# SCH_ENAK-display_2025-10-05.net
KiCad netlist of a schematic drawn in EasyEDA
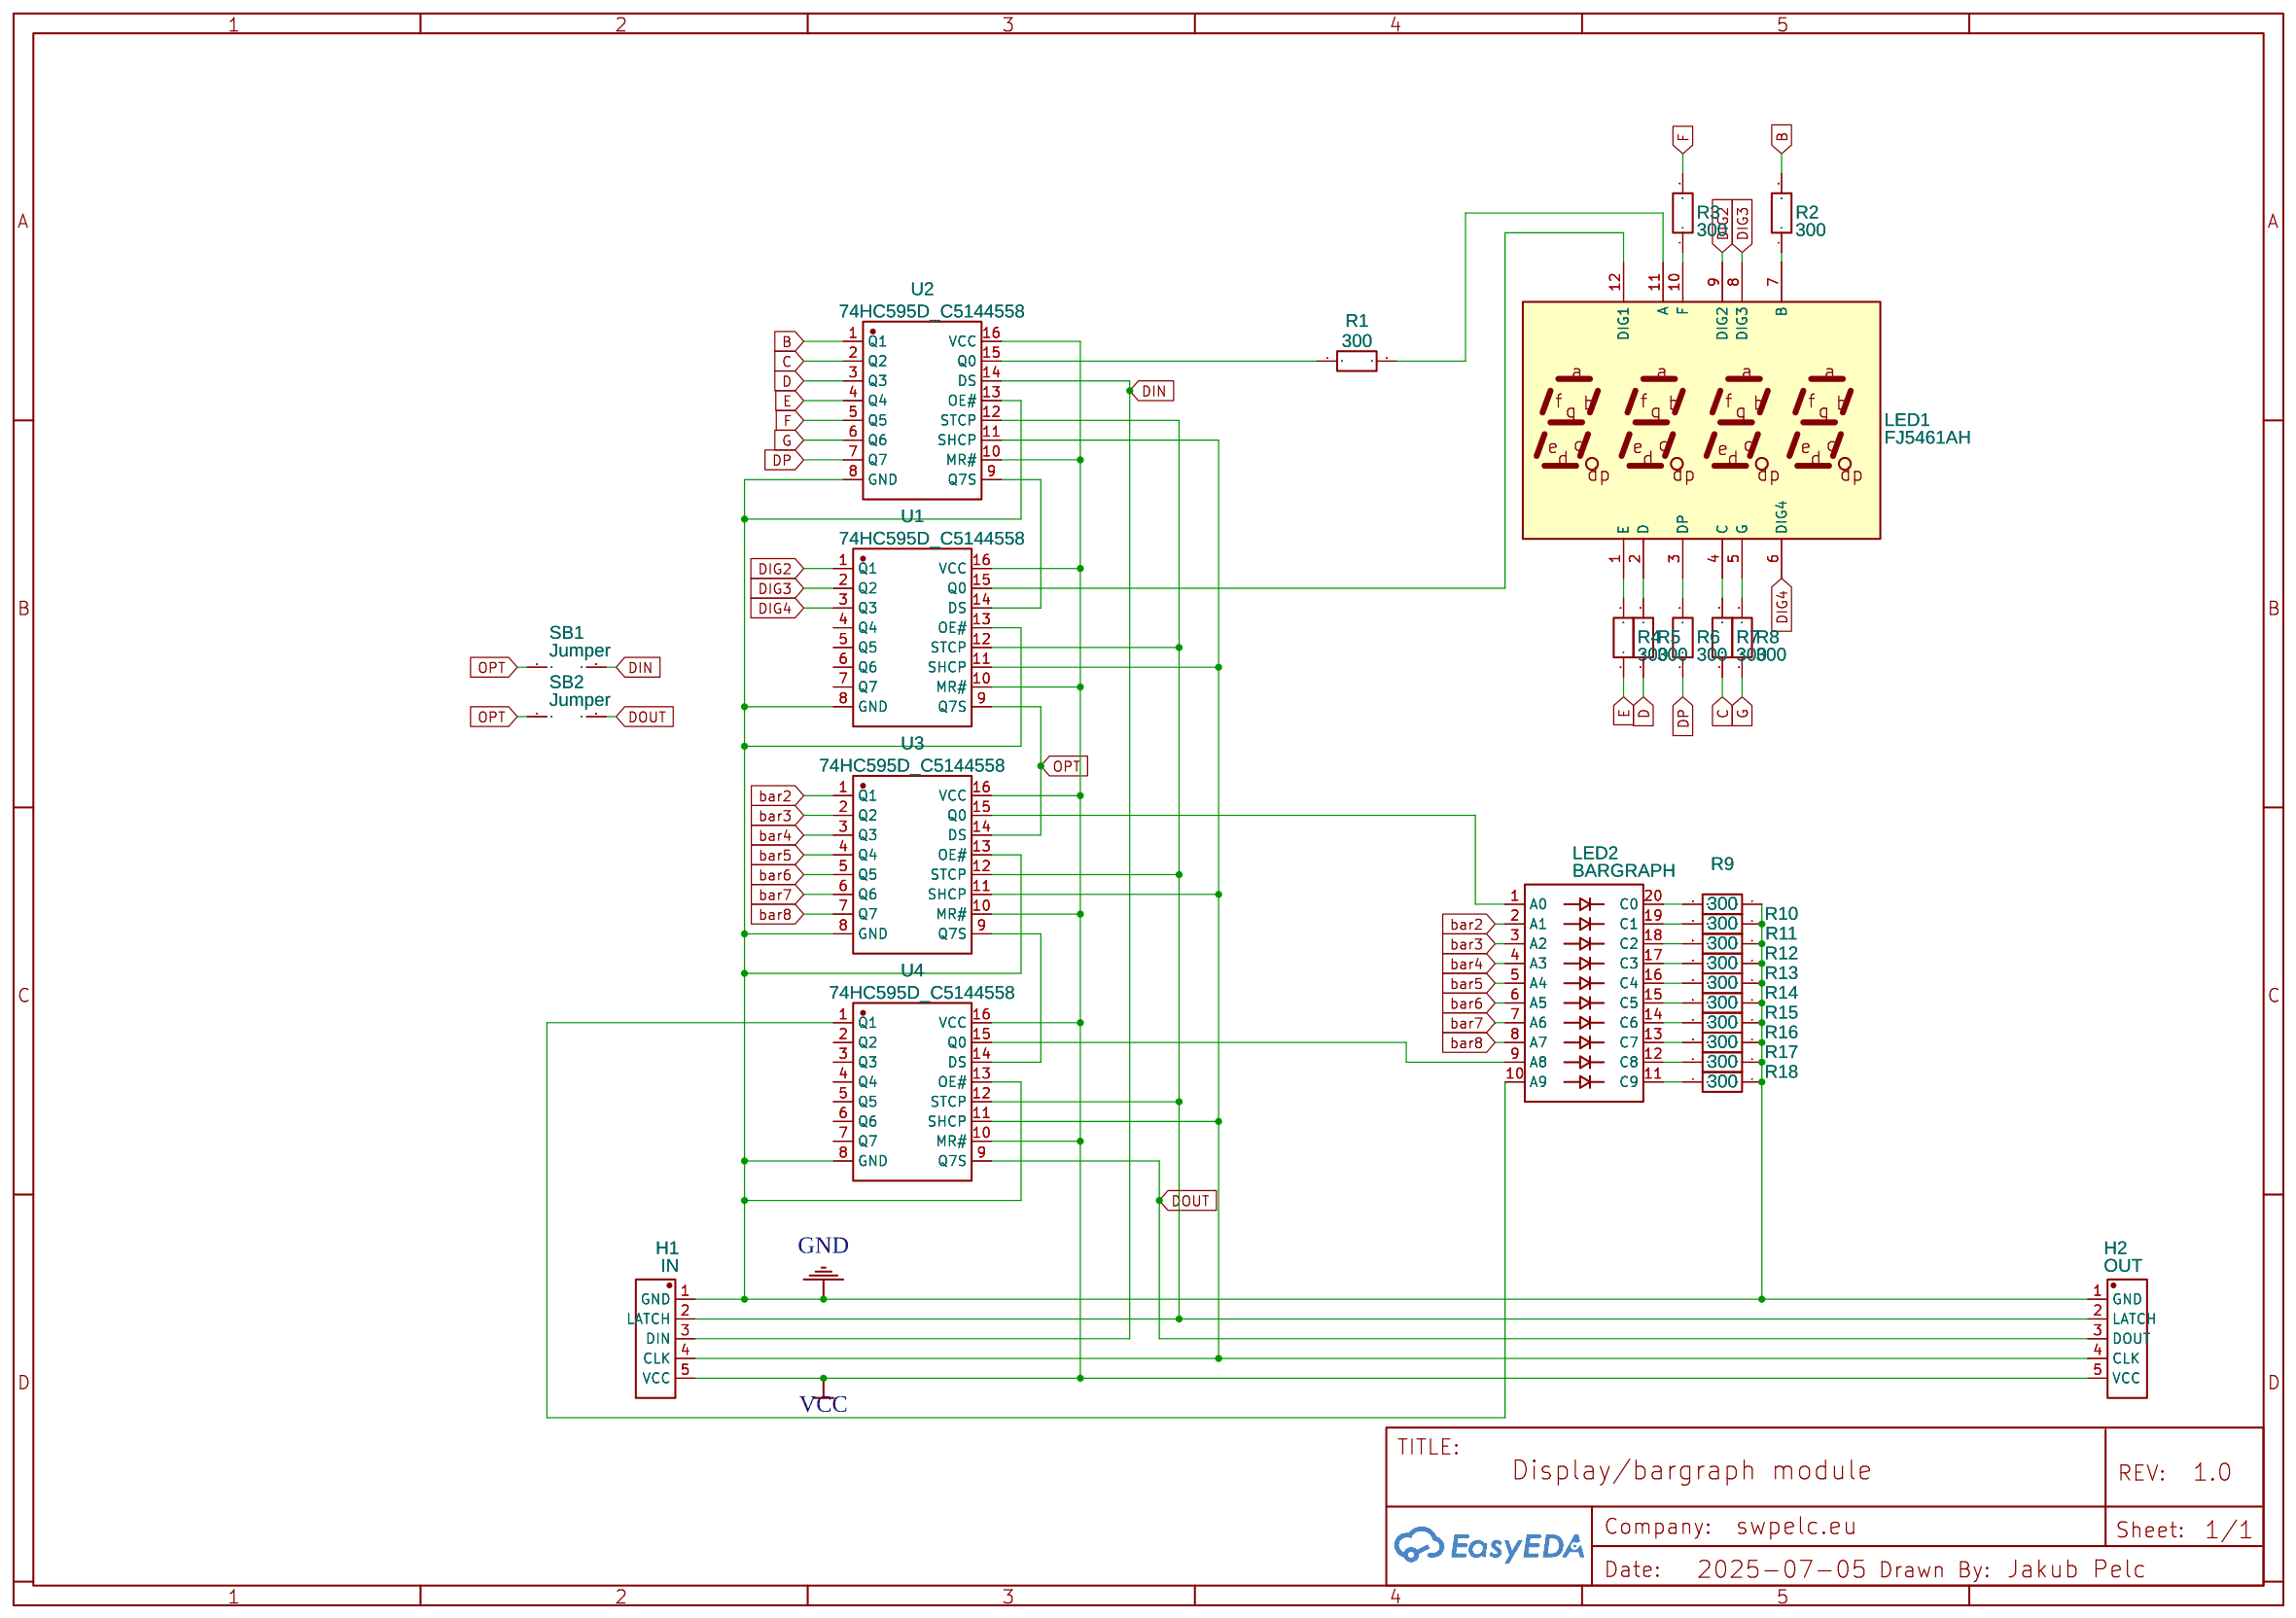
[diagram p0: schematic sheet]

(export (version "E")
  (design (tool "Eeschema 10.0.6"))
  (components
    (comp (ref "H1") (value "IN") (libsource (lib "") (part "HEADER - 2.54_1X5_1")))
    (comp (ref "H2") (value "OUT") (libsource (lib "") (part "HEADER - 2.54_1X5")))
    (comp (ref "LED1")
      (value "FJ5461AH")
      (fields (field (name "Manufacturer Part") "FJ5461AH 橙红") (field (name "Manufacturer") "志浩"))
      (libsource (lib "") (part "FJ5461AH"))
    )
    (comp (ref "LED2") (value "BARGRAPH") (libsource (lib "") (part "BARGRAPH")))
    (comp (ref "R1") (value "300") (libsource (lib "") (part "R_0603_EU_2")))
    (comp (ref "R2") (value "300") (libsource (lib "") (part "R_0603_EU_1")))
    (comp (ref "R3") (value "300") (libsource (lib "") (part "R_0603_EU_1")))
    (comp (ref "R4") (value "300") (libsource (lib "") (part "R_0603_EU_1")))
    (comp (ref "R5") (value "300") (libsource (lib "") (part "R_0603_EU_1")))
    (comp (ref "R6") (value "300") (libsource (lib "") (part "R_0603_EU_1")))
    (comp (ref "R7") (value "300") (libsource (lib "") (part "R_0603_EU_1")))
    (comp (ref "R8") (value "300") (libsource (lib "") (part "R_0603_EU_1")))
    (comp (ref "R9") (value "300") (libsource (lib "") (part "R_0603_EU")))
    (comp (ref "R10") (value "300") (libsource (lib "") (part "R_0603_EU")))
    (comp (ref "R11") (value "300") (libsource (lib "") (part "R_0603_EU")))
    (comp (ref "R12") (value "300") (libsource (lib "") (part "R_0603_EU")))
    (comp (ref "R13") (value "300") (libsource (lib "") (part "R_0603_EU")))
    (comp (ref "R14") (value "300") (libsource (lib "") (part "R_0603_EU")))
    (comp (ref "R15") (value "300") (libsource (lib "") (part "R_0603_EU")))
    (comp (ref "R16") (value "300") (libsource (lib "") (part "R_0603_EU")))
    (comp (ref "R17") (value "300") (libsource (lib "") (part "R_0603_EU")))
    (comp (ref "R18") (value "300") (libsource (lib "") (part "R_0603_EU")))
    (comp (ref "SB1")
      (value "Jumper")
      (fields (field (name "Manufacturer Part") "0603WAF0000T5E") (field (name "Manufacturer") "NONE"))
      (libsource (lib "") (part "SMD JUMPER OPEN 2 PIN"))
    )
    (comp (ref "SB2")
      (value "Jumper")
      (fields (field (name "Manufacturer Part") "0603WAF0000T5E") (field (name "Manufacturer") "NONE"))
      (libsource (lib "") (part "SMD JUMPER OPEN 2 PIN"))
    )
    (comp (ref "U1")
      (value "74HC595D_C5144558")
      (fields (field (name "Manufacturer Part") "74HC595D") (field (name "Manufacturer") "JSMSEMI(杰盛微)"))
      (libsource (lib "") (part "74HC595D_C5144558"))
    )
    (comp (ref "U2")
      (value "74HC595D_C5144558")
      (fields (field (name "Manufacturer Part") "74HC595D") (field (name "Manufacturer") "JSMSEMI(杰盛微)"))
      (libsource (lib "") (part "74HC595D_C5144558"))
    )
    (comp (ref "U3")
      (value "74HC595D_C5144558")
      (fields (field (name "Manufacturer Part") "74HC595D") (field (name "Manufacturer") "JSMSEMI(杰盛微)"))
      (libsource (lib "") (part "74HC595D_C5144558"))
    )
    (comp (ref "U4")
      (value "74HC595D_C5144558")
      (fields (field (name "Manufacturer Part") "74HC595D") (field (name "Manufacturer") "JSMSEMI(杰盛微)"))
      (libsource (lib "") (part "74HC595D_C5144558"))
    )
  )
  (nets
    (net (code "1") (name "B") (class "Default")
      (node (ref "R2") (pin "2") (pinfunction "2_2") (pintype "unspecified"))
      (node (ref "U2") (pin "1") (pinfunction "Q1_1") (pintype "unspecified"))
    )
    (net (code "2") (name "C") (class "Default")
      (node (ref "R7") (pin "1") (pinfunction "1_1") (pintype "unspecified"))
      (node (ref "U2") (pin "2") (pinfunction "Q2_2") (pintype "unspecified"))
    )
    (net (code "3") (name "D") (class "Default")
      (node (ref "R5") (pin "1") (pinfunction "1_1") (pintype "unspecified"))
      (node (ref "U2") (pin "3") (pinfunction "Q3_3") (pintype "unspecified"))
    )
    (net (code "4") (name "DIG2") (class "Default")
      (node (ref "LED1") (pin "9") (pinfunction "DIG2_9") (pintype "input"))
      (node (ref "U1") (pin "1") (pinfunction "Q1_1") (pintype "unspecified"))
    )
    (net (code "5") (name "DIG3") (class "Default")
      (node (ref "LED1") (pin "8") (pinfunction "DIG3_8") (pintype "input"))
      (node (ref "U1") (pin "2") (pinfunction "Q2_2") (pintype "unspecified"))
    )
    (net (code "6") (name "DIG4") (class "Default")
      (node (ref "LED1") (pin "6") (pinfunction "DIG4_6") (pintype "input"))
      (node (ref "U1") (pin "3") (pinfunction "Q3_3") (pintype "unspecified"))
    )
    (net (code "7") (name "DIN") (class "Default")
      (node (ref "H1") (pin "3") (pinfunction "DIN_3") (pintype "unspecified"))
      (node (ref "SB1") (pin "2") (pinfunction "N_2") (pintype "input"))
      (node (ref "U2") (pin "14") (pinfunction "DS_14") (pintype "unspecified"))
    )
    (net (code "8") (name "DOUT") (class "Default")
      (node (ref "H2") (pin "3") (pinfunction "DOUT_3") (pintype "unspecified"))
      (node (ref "SB2") (pin "2") (pinfunction "N_2") (pintype "input"))
      (node (ref "U4") (pin "9") (pinfunction "Q7S_9") (pintype "unspecified"))
    )
    (net (code "9") (name "DP") (class "Default")
      (node (ref "R6") (pin "1") (pinfunction "1_1") (pintype "unspecified"))
      (node (ref "U2") (pin "7") (pinfunction "Q7_7") (pintype "unspecified"))
    )
    (net (code "10") (name "E") (class "Default")
      (node (ref "R4") (pin "1") (pinfunction "1_1") (pintype "unspecified"))
      (node (ref "U2") (pin "4") (pinfunction "Q4_4") (pintype "unspecified"))
    )
    (net (code "11") (name "F") (class "Default")
      (node (ref "R3") (pin "2") (pinfunction "2_2") (pintype "unspecified"))
      (node (ref "U2") (pin "5") (pinfunction "Q5_5") (pintype "unspecified"))
    )
    (net (code "12") (name "G") (class "Default")
      (node (ref "R8") (pin "1") (pinfunction "1_1") (pintype "unspecified"))
      (node (ref "U2") (pin "6") (pinfunction "Q6_6") (pintype "unspecified"))
    )
    (net (code "13") (name "GND") (class "Default")
      (node (ref "H1") (pin "1") (pinfunction "GND_1") (pintype "unspecified"))
      (node (ref "H2") (pin "1") (pinfunction "GND_1") (pintype "unspecified"))
      (node (ref "R10") (pin "1") (pinfunction "1_1") (pintype "unspecified"))
      (node (ref "R11") (pin "1") (pinfunction "1_1") (pintype "unspecified"))
      (node (ref "R12") (pin "1") (pinfunction "1_1") (pintype "unspecified"))
      (node (ref "R13") (pin "1") (pinfunction "1_1") (pintype "unspecified"))
      (node (ref "R14") (pin "1") (pinfunction "1_1") (pintype "unspecified"))
      (node (ref "R15") (pin "1") (pinfunction "1_1") (pintype "unspecified"))
      (node (ref "R16") (pin "1") (pinfunction "1_1") (pintype "unspecified"))
      (node (ref "R17") (pin "1") (pinfunction "1_1") (pintype "unspecified"))
      (node (ref "R18") (pin "1") (pinfunction "1_1") (pintype "unspecified"))
      (node (ref "R9") (pin "1") (pinfunction "1_1") (pintype "unspecified"))
      (node (ref "U1") (pin "13") (pinfunction "OE#_13") (pintype "unspecified"))
      (node (ref "U1") (pin "8") (pinfunction "GND_8") (pintype "unspecified"))
      (node (ref "U2") (pin "13") (pinfunction "OE#_13") (pintype "unspecified"))
      (node (ref "U2") (pin "8") (pinfunction "GND_8") (pintype "unspecified"))
      (node (ref "U3") (pin "13") (pinfunction "OE#_13") (pintype "unspecified"))
      (node (ref "U3") (pin "8") (pinfunction "GND_8") (pintype "unspecified"))
      (node (ref "U4") (pin "13") (pinfunction "OE#_13") (pintype "unspecified"))
      (node (ref "U4") (pin "8") (pinfunction "GND_8") (pintype "unspecified"))
    )
    (net (code "14") (name "Net-(H1-CLK)") (class "Default")
      (node (ref "H1") (pin "4") (pinfunction "CLK_4") (pintype "unspecified"))
      (node (ref "H2") (pin "4") (pinfunction "CLK_4") (pintype "unspecified"))
      (node (ref "U1") (pin "11") (pinfunction "SHCP_11") (pintype "unspecified"))
      (node (ref "U2") (pin "11") (pinfunction "SHCP_11") (pintype "unspecified"))
      (node (ref "U3") (pin "11") (pinfunction "SHCP_11") (pintype "unspecified"))
      (node (ref "U4") (pin "11") (pinfunction "SHCP_11") (pintype "unspecified"))
    )
    (net (code "15") (name "Net-(H1-LATCH)") (class "Default")
      (node (ref "H1") (pin "2") (pinfunction "LATCH_2") (pintype "unspecified"))
      (node (ref "H2") (pin "2") (pinfunction "LATCH_2") (pintype "unspecified"))
      (node (ref "U1") (pin "12") (pinfunction "STCP_12") (pintype "unspecified"))
      (node (ref "U2") (pin "12") (pinfunction "STCP_12") (pintype "unspecified"))
      (node (ref "U3") (pin "12") (pinfunction "STCP_12") (pintype "unspecified"))
      (node (ref "U4") (pin "12") (pinfunction "STCP_12") (pintype "unspecified"))
    )
    (net (code "16") (name "Net-(LED1-A)") (class "Default")
      (node (ref "LED1") (pin "11") (pinfunction "A_11") (pintype "input"))
      (node (ref "R1") (pin "2") (pinfunction "2_2") (pintype "unspecified"))
    )
    (net (code "17") (name "Net-(LED1-B)") (class "Default")
      (node (ref "LED1") (pin "7") (pinfunction "B_7") (pintype "input"))
      (node (ref "R2") (pin "1") (pinfunction "1_1") (pintype "unspecified"))
    )
    (net (code "18") (name "Net-(LED1-C)") (class "Default")
      (node (ref "LED1") (pin "4") (pinfunction "C_4") (pintype "input"))
      (node (ref "R7") (pin "2") (pinfunction "2_2") (pintype "unspecified"))
    )
    (net (code "19") (name "Net-(LED1-D)") (class "Default")
      (node (ref "LED1") (pin "2") (pinfunction "D_2") (pintype "input"))
      (node (ref "R5") (pin "2") (pinfunction "2_2") (pintype "unspecified"))
    )
    (net (code "20") (name "Net-(LED1-DIG1)") (class "Default")
      (node (ref "LED1") (pin "12") (pinfunction "DIG1_12") (pintype "input"))
      (node (ref "U1") (pin "15") (pinfunction "Q0_15") (pintype "unspecified"))
    )
    (net (code "21") (name "Net-(LED1-DP)") (class "Default")
      (node (ref "LED1") (pin "3") (pinfunction "DP_3") (pintype "input"))
      (node (ref "R6") (pin "2") (pinfunction "2_2") (pintype "unspecified"))
    )
    (net (code "22") (name "Net-(LED1-E)") (class "Default")
      (node (ref "LED1") (pin "1") (pinfunction "E_1") (pintype "input"))
      (node (ref "R4") (pin "2") (pinfunction "2_2") (pintype "unspecified"))
    )
    (net (code "23") (name "Net-(LED1-F)") (class "Default")
      (node (ref "LED1") (pin "10") (pinfunction "F_10") (pintype "input"))
      (node (ref "R3") (pin "1") (pinfunction "1_1") (pintype "unspecified"))
    )
    (net (code "24") (name "Net-(LED1-G)") (class "Default")
      (node (ref "LED1") (pin "5") (pinfunction "G_5") (pintype "input"))
      (node (ref "R8") (pin "2") (pinfunction "2_2") (pintype "unspecified"))
    )
    (net (code "25") (name "Net-(LED2-A0)") (class "Default")
      (node (ref "LED2") (pin "1") (pinfunction "A0_1") (pintype "unspecified"))
      (node (ref "U3") (pin "15") (pinfunction "Q0_15") (pintype "unspecified"))
    )
    (net (code "26") (name "Net-(LED2-A8)") (class "Default")
      (node (ref "LED2") (pin "9") (pinfunction "A8_9") (pintype "unspecified"))
      (node (ref "U4") (pin "15") (pinfunction "Q0_15") (pintype "unspecified"))
    )
    (net (code "27") (name "Net-(LED2-A9)") (class "Default")
      (node (ref "LED2") (pin "10") (pinfunction "A9_10") (pintype "unspecified"))
      (node (ref "U4") (pin "1") (pinfunction "Q1_1") (pintype "unspecified"))
    )
    (net (code "28") (name "Net-(LED2-C0)") (class "Default")
      (node (ref "LED2") (pin "20") (pinfunction "C0_20") (pintype "unspecified"))
      (node (ref "R9") (pin "2") (pinfunction "2_2") (pintype "unspecified"))
    )
    (net (code "29") (name "Net-(LED2-C1)") (class "Default")
      (node (ref "LED2") (pin "19") (pinfunction "C1_19") (pintype "unspecified"))
      (node (ref "R10") (pin "2") (pinfunction "2_2") (pintype "unspecified"))
    )
    (net (code "30") (name "Net-(LED2-C2)") (class "Default")
      (node (ref "LED2") (pin "18") (pinfunction "C2_18") (pintype "unspecified"))
      (node (ref "R11") (pin "2") (pinfunction "2_2") (pintype "unspecified"))
    )
    (net (code "31") (name "Net-(LED2-C3)") (class "Default")
      (node (ref "LED2") (pin "17") (pinfunction "C3_17") (pintype "unspecified"))
      (node (ref "R12") (pin "2") (pinfunction "2_2") (pintype "unspecified"))
    )
    (net (code "32") (name "Net-(LED2-C4)") (class "Default")
      (node (ref "LED2") (pin "16") (pinfunction "C4_16") (pintype "unspecified"))
      (node (ref "R13") (pin "2") (pinfunction "2_2") (pintype "unspecified"))
    )
    (net (code "33") (name "Net-(LED2-C5)") (class "Default")
      (node (ref "LED2") (pin "15") (pinfunction "C5_15") (pintype "unspecified"))
      (node (ref "R14") (pin "2") (pinfunction "2_2") (pintype "unspecified"))
    )
    (net (code "34") (name "Net-(LED2-C6)") (class "Default")
      (node (ref "LED2") (pin "14") (pinfunction "C6_14") (pintype "unspecified"))
      (node (ref "R15") (pin "2") (pinfunction "2_2") (pintype "unspecified"))
    )
    (net (code "35") (name "Net-(LED2-C7)") (class "Default")
      (node (ref "LED2") (pin "13") (pinfunction "C7_13") (pintype "unspecified"))
      (node (ref "R16") (pin "2") (pinfunction "2_2") (pintype "unspecified"))
    )
    (net (code "36") (name "Net-(LED2-C8)") (class "Default")
      (node (ref "LED2") (pin "12") (pinfunction "C8_12") (pintype "unspecified"))
      (node (ref "R17") (pin "2") (pinfunction "2_2") (pintype "unspecified"))
    )
    (net (code "37") (name "Net-(LED2-C9)") (class "Default")
      (node (ref "LED2") (pin "11") (pinfunction "C9_11") (pintype "unspecified"))
      (node (ref "R18") (pin "2") (pinfunction "2_2") (pintype "unspecified"))
    )
    (net (code "38") (name "Net-(U1-DS)") (class "Default")
      (node (ref "U1") (pin "14") (pinfunction "DS_14") (pintype "unspecified"))
      (node (ref "U2") (pin "9") (pinfunction "Q7S_9") (pintype "unspecified"))
    )
    (net (code "39") (name "Net-(U2-Q0)") (class "Default")
      (node (ref "R1") (pin "1") (pinfunction "1_1") (pintype "unspecified"))
      (node (ref "U2") (pin "15") (pinfunction "Q0_15") (pintype "unspecified"))
    )
    (net (code "40") (name "Net-(U3-Q7S)") (class "Default")
      (node (ref "U3") (pin "9") (pinfunction "Q7S_9") (pintype "unspecified"))
      (node (ref "U4") (pin "14") (pinfunction "DS_14") (pintype "unspecified"))
    )
    (net (code "41") (name "OPT") (class "Default")
      (node (ref "SB1") (pin "1") (pinfunction "P_1") (pintype "input"))
      (node (ref "SB2") (pin "1") (pinfunction "P_1") (pintype "input"))
      (node (ref "U1") (pin "9") (pinfunction "Q7S_9") (pintype "unspecified"))
      (node (ref "U3") (pin "14") (pinfunction "DS_14") (pintype "unspecified"))
    )
    (net (code "42") (name "VCC") (class "Default")
      (node (ref "H1") (pin "5") (pinfunction "VCC_5") (pintype "unspecified"))
      (node (ref "H2") (pin "5") (pinfunction "VCC_5") (pintype "unspecified"))
      (node (ref "U1") (pin "10") (pinfunction "MR#_10") (pintype "unspecified"))
      (node (ref "U1") (pin "16") (pinfunction "VCC_16") (pintype "unspecified"))
      (node (ref "U2") (pin "10") (pinfunction "MR#_10") (pintype "unspecified"))
      (node (ref "U2") (pin "16") (pinfunction "VCC_16") (pintype "unspecified"))
      (node (ref "U3") (pin "10") (pinfunction "MR#_10") (pintype "unspecified"))
      (node (ref "U3") (pin "16") (pinfunction "VCC_16") (pintype "unspecified"))
      (node (ref "U4") (pin "10") (pinfunction "MR#_10") (pintype "unspecified"))
      (node (ref "U4") (pin "16") (pinfunction "VCC_16") (pintype "unspecified"))
    )
    (net (code "43") (name "bar2") (class "Default")
      (node (ref "LED2") (pin "2") (pinfunction "A1_2") (pintype "unspecified"))
      (node (ref "U3") (pin "1") (pinfunction "Q1_1") (pintype "unspecified"))
    )
    (net (code "44") (name "bar3") (class "Default")
      (node (ref "LED2") (pin "3") (pinfunction "A2_3") (pintype "unspecified"))
      (node (ref "U3") (pin "2") (pinfunction "Q2_2") (pintype "unspecified"))
    )
    (net (code "45") (name "bar4") (class "Default")
      (node (ref "LED2") (pin "4") (pinfunction "A3_4") (pintype "unspecified"))
      (node (ref "U3") (pin "3") (pinfunction "Q3_3") (pintype "unspecified"))
    )
    (net (code "46") (name "bar5") (class "Default")
      (node (ref "LED2") (pin "5") (pinfunction "A4_5") (pintype "unspecified"))
      (node (ref "U3") (pin "4") (pinfunction "Q4_4") (pintype "unspecified"))
    )
    (net (code "47") (name "bar6") (class "Default")
      (node (ref "LED2") (pin "6") (pinfunction "A5_6") (pintype "unspecified"))
      (node (ref "U3") (pin "5") (pinfunction "Q5_5") (pintype "unspecified"))
    )
    (net (code "48") (name "bar7") (class "Default")
      (node (ref "LED2") (pin "7") (pinfunction "A6_7") (pintype "unspecified"))
      (node (ref "U3") (pin "6") (pinfunction "Q6_6") (pintype "unspecified"))
    )
    (net (code "49") (name "bar8") (class "Default")
      (node (ref "LED2") (pin "8") (pinfunction "A7_8") (pintype "unspecified"))
      (node (ref "U3") (pin "7") (pinfunction "Q7_7") (pintype "unspecified"))
    )
    (net (code "50") (name "unconnected-(U1-Q4-Pad4)") (class "Default")
      (node (ref "U1") (pin "4") (pinfunction "Q4_4") (pintype "unspecified"))
    )
    (net (code "51") (name "unconnected-(U1-Q5-Pad5)") (class "Default")
      (node (ref "U1") (pin "5") (pinfunction "Q5_5") (pintype "unspecified"))
    )
    (net (code "52") (name "unconnected-(U1-Q6-Pad6)") (class "Default")
      (node (ref "U1") (pin "6") (pinfunction "Q6_6") (pintype "unspecified"))
    )
    (net (code "53") (name "unconnected-(U1-Q7-Pad7)") (class "Default")
      (node (ref "U1") (pin "7") (pinfunction "Q7_7") (pintype "unspecified"))
    )
    (net (code "54") (name "unconnected-(U4-Q2-Pad2)") (class "Default")
      (node (ref "U4") (pin "2") (pinfunction "Q2_2") (pintype "unspecified"))
    )
    (net (code "55") (name "unconnected-(U4-Q3-Pad3)") (class "Default")
      (node (ref "U4") (pin "3") (pinfunction "Q3_3") (pintype "unspecified"))
    )
    (net (code "56") (name "unconnected-(U4-Q4-Pad4)") (class "Default")
      (node (ref "U4") (pin "4") (pinfunction "Q4_4") (pintype "unspecified"))
    )
    (net (code "57") (name "unconnected-(U4-Q5-Pad5)") (class "Default")
      (node (ref "U4") (pin "5") (pinfunction "Q5_5") (pintype "unspecified"))
    )
    (net (code "58") (name "unconnected-(U4-Q6-Pad6)") (class "Default")
      (node (ref "U4") (pin "6") (pinfunction "Q6_6") (pintype "unspecified"))
    )
    (net (code "59") (name "unconnected-(U4-Q7-Pad7)") (class "Default")
      (node (ref "U4") (pin "7") (pinfunction "Q7_7") (pintype "unspecified"))
    )
  )
)
